# Sera.net
KiCad netlist of a schematic drawn in Altium Designer
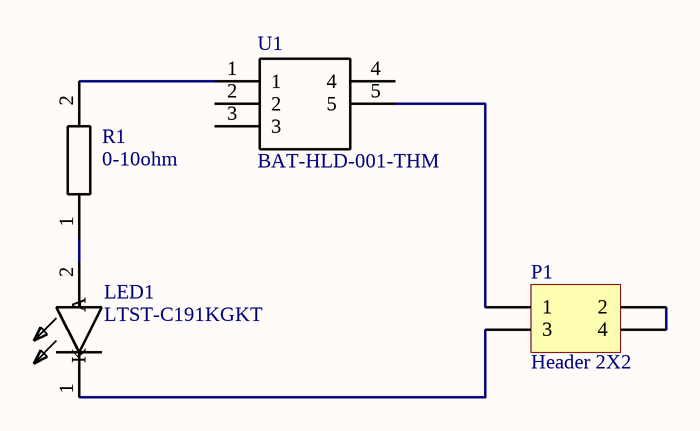
[diagram p0: Sera.SchDoc]

(export (version "E")
  (design (tool "Eeschema 10.0.6"))
  (components
    (comp (ref "LED1")
      (value "LTST-C191KGKT")
      (footprint "SamacSys:LEDC1608X55N")
      (description "LED")
      (fields
        (field (name "MOUSER PART NUMBER") "859-LTST-C191KGKT")
        (field (name "RS PART NUMBER") "6921010P")
      )
      (libsource (lib "*") (part "LTST-C191KGKT"))
    )
    (comp (ref "P1")
      (value "Header 2X2")
      (footprint "HDR2X2")
      (description "Header, 2-Pin, Dual row")
      (fields (field (name "PUBLISHER") "Altium Limited"))
      (libsource (lib "Miscellaneous Connectors") (part "Header 2X2"))
    )
    (comp (ref "R1")
      (value "0-10ohm")
      (footprint "SamacSys:RESC2012X60N")
      (description "Resistor")
      (fields
        (field (name "MANUFACTURER_PART_NUMBER") "CRCW0805160RFKEAHP")
        (field (name "MOUSER PART NUMBER") "71-CRCW0805160RFKEAH")
      )
      (libsource (lib "*") (part "CRCW0805160RFKEAHP"))
    )
    (comp (ref "U1")
      (value "BAT-HLD-001-THM")
      (footprint "SamacSys:BATHLD001THM")
      (description "Undefined or Miscellaneous")
      (fields (field (name "MOUSER PART NUMBER") "712-BAT-HLD-001-THM"))
      (libsource (lib "*") (part "BAT-HLD-001-THM"))
    )
  )
  (nets
    (net (code "1") (name "Net-(LED1-A)") (class "Default")
      (node (ref "LED1") (pin "2") (pinfunction "A_2") (pintype "passive"))
      (node (ref "R1") (pin "1") (pinfunction "1_1") (pintype "passive"))
    )
    (net (code "2") (name "Net-(LED1-K)") (class "Default")
      (node (ref "LED1") (pin "1") (pinfunction "K_1") (pintype "passive"))
      (node (ref "P1") (pin "3") (pinfunction "3_3") (pintype "passive"))
    )
    (net (code "3") (name "Net-(P1-Pad1)") (class "Default")
      (node (ref "P1") (pin "1") (pinfunction "1_1") (pintype "passive"))
      (node (ref "U1") (pin "5") (pinfunction "5_5") (pintype "passive"))
    )
    (net (code "4") (name "Net-(P1-Pad2)") (class "Default")
      (node (ref "P1") (pin "2") (pinfunction "2_2") (pintype "passive"))
      (node (ref "P1") (pin "4") (pinfunction "4_4") (pintype "passive"))
    )
    (net (code "5") (name "Net-(R1-Pad2)") (class "Default")
      (node (ref "R1") (pin "2") (pinfunction "2_2") (pintype "passive"))
      (node (ref "U1") (pin "1") (pinfunction "1_1") (pintype "passive"))
    )
    (net (code "6") (name "unconnected-(U1-Pad2)") (class "Default")
      (node (ref "U1") (pin "2") (pinfunction "2_2") (pintype "passive"))
    )
    (net (code "7") (name "unconnected-(U1-Pad3)") (class "Default")
      (node (ref "U1") (pin "3") (pinfunction "3_3") (pintype "passive"))
    )
    (net (code "8") (name "unconnected-(U1-Pad4)") (class "Default")
      (node (ref "U1") (pin "4") (pinfunction "4_4") (pintype "passive"))
    )
  )
)
